# Statron_RP2040.net
KiCad netlist of a schematic drawn in Altium Designer
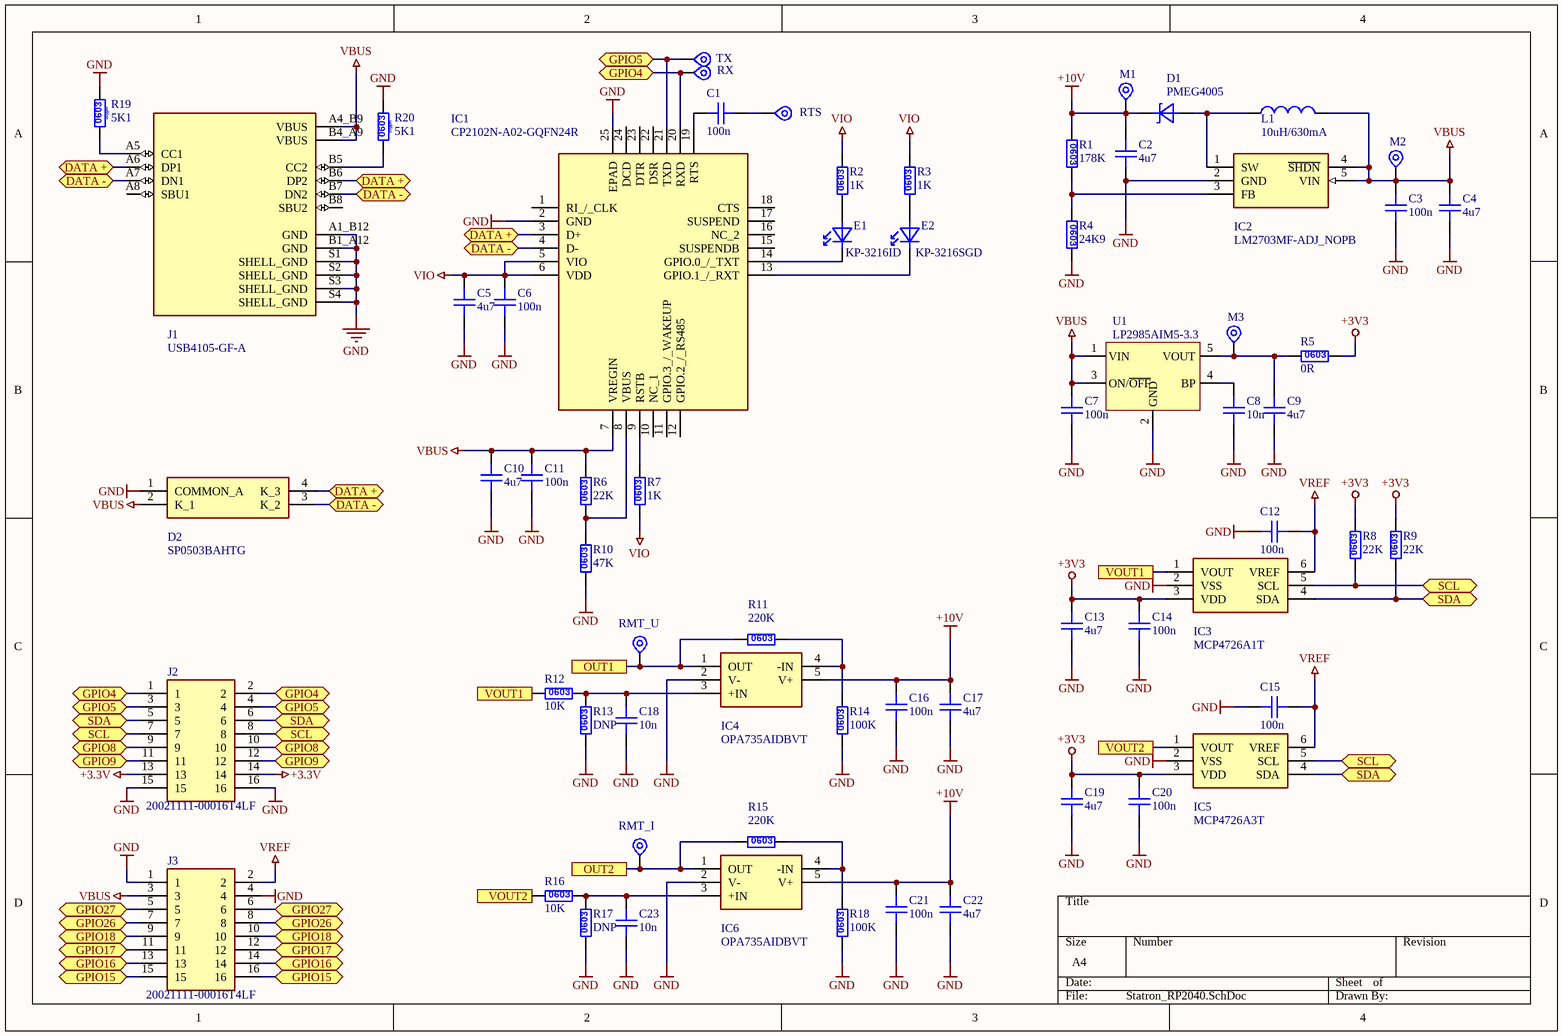
[diagram p0: Statron_RP2040.SchDoc]

(export (version "E")
  (design (tool "Eeschema 10.0.6"))
  (components
    (comp (ref "C1")
      (value "100n")
      (footprint "RP2040:C0603M")
      (description "Ceramic Capacitor X7R")
      (fields (field (name "MANUFACTURER") "VISHAY") (field (name "PART NUMBER") "100n/16V X7R C0603"))
      (libsource (lib "PCB_RP2040") (part "CMP-UN-000268-1"))
    )
    (comp (ref "C2")
      (value "4u7")
      (footprint "RP2040:C0603")
      (description "Ceramic Capacitor X5R")
      (fields (field (name "PART NUMBER") "GRM188R60J475KE19J") (field (name "MANUFACTURER") "Murata"))
      (libsource (lib "PCB_RP2040") (part "CMP-UN-000401-1"))
    )
    (comp (ref "C3")
      (value "100n")
      (footprint "RP2040:C0603M")
      (description "Ceramic Capacitor X7R")
      (fields (field (name "MANUFACTURER") "VISHAY") (field (name "PART NUMBER") "100n/16V X7R C0603"))
      (libsource (lib "PCB_RP2040") (part "CMP-UN-000268-1"))
    )
    (comp (ref "C4")
      (value "4u7")
      (footprint "RP2040:C0603")
      (description "Ceramic Capacitor X5R")
      (fields (field (name "PART NUMBER") "GRM188R60J475KE19J") (field (name "MANUFACTURER") "Murata"))
      (libsource (lib "PCB_RP2040") (part "CMP-UN-000401-1"))
    )
    (comp (ref "C5")
      (value "4u7")
      (footprint "RP2040:C0603")
      (description "Ceramic Capacitor X5R")
      (fields (field (name "PART NUMBER") "GRM188R60J475KE19J") (field (name "MANUFACTURER") "Murata"))
      (libsource (lib "PCB_RP2040") (part "CMP-UN-000401-1"))
    )
    (comp (ref "C6")
      (value "100n")
      (footprint "RP2040:C0603M")
      (description "Ceramic Capacitor X7R")
      (fields (field (name "MANUFACTURER") "VISHAY") (field (name "PART NUMBER") "100n/16V X7R C0603"))
      (libsource (lib "PCB_RP2040") (part "CMP-UN-000268-1"))
    )
    (comp (ref "C7")
      (value "100n")
      (footprint "RP2040:C0603M")
      (description "Ceramic Capacitor X7R")
      (fields (field (name "MANUFACTURER") "VISHAY") (field (name "PART NUMBER") "100n/16V X7R C0603"))
      (libsource (lib "PCB_RP2040") (part "UniversalCapacitor"))
    )
    (comp (ref "C8")
      (value "10n")
      (footprint "RP2040:C0603M")
      (description "Ceramic Capacitor X7R")
      (fields (field (name "MANUFACTURER") "VISHAY") (field (name "PART NUMBER") "10n/50V X7R C0603"))
      (libsource (lib "PCB_RP2040") (part "UniversalCapacitor"))
    )
    (comp (ref "C9")
      (value "4u7")
      (footprint "RP2040:C0603")
      (description "Ceramic Capacitor X5R")
      (fields (field (name "PART NUMBER") "GRM188R60J475KE19J") (field (name "MANUFACTURER") "Murata"))
      (libsource (lib "PCB_RP2040") (part "CMP-UN-000401-1"))
    )
    (comp (ref "C10")
      (value "4u7")
      (footprint "RP2040:C0603")
      (description "Ceramic Capacitor X5R")
      (fields (field (name "PART NUMBER") "GRM188R60J475KE19J") (field (name "MANUFACTURER") "Murata"))
      (libsource (lib "PCB_RP2040") (part "CMP-UN-000401-1"))
    )
    (comp (ref "C11")
      (value "100n")
      (footprint "RP2040:C0603M")
      (description "Ceramic Capacitor X7R")
      (fields (field (name "MANUFACTURER") "VISHAY") (field (name "PART NUMBER") "100n/16V X7R C0603"))
      (libsource (lib "PCB_RP2040") (part "CMP-UN-000268-1"))
    )
    (comp (ref "C12")
      (value "100n")
      (footprint "RP2040:C0603M")
      (description "Ceramic Capacitor X7R")
      (fields (field (name "MANUFACTURER") "VISHAY") (field (name "PART NUMBER") "100n/16V X7R C0603"))
      (libsource (lib "PCB_RP2040") (part "CMP-UN-000268-1"))
    )
    (comp (ref "C13")
      (value "4u7")
      (footprint "RP2040:C0603")
      (description "Ceramic Capacitor X5R")
      (fields (field (name "PART NUMBER") "GRM188R60J475KE19J") (field (name "MANUFACTURER") "Murata"))
      (libsource (lib "PCB_RP2040") (part "CMP-UN-000401-1"))
    )
    (comp (ref "C14")
      (value "100n")
      (footprint "RP2040:C0603M")
      (description "Ceramic Capacitor X7R")
      (fields (field (name "MANUFACTURER") "VISHAY") (field (name "PART NUMBER") "100n/16V X7R C0603"))
      (libsource (lib "PCB_RP2040") (part "CMP-UN-000268-1"))
    )
    (comp (ref "C15")
      (value "100n")
      (footprint "RP2040:C0603M")
      (description "Ceramic Capacitor X7R")
      (fields (field (name "MANUFACTURER") "VISHAY") (field (name "PART NUMBER") "100n/16V X7R C0603"))
      (libsource (lib "PCB_RP2040") (part "CMP-UN-000268-1"))
    )
    (comp (ref "C16")
      (value "100n")
      (footprint "RP2040:C0603M")
      (description "Ceramic Capacitor X7R")
      (fields (field (name "MANUFACTURER") "VISHAY") (field (name "PART NUMBER") "100n/16V X7R C0603"))
      (libsource (lib "PCB_RP2040") (part "CMP-UN-000268-1"))
    )
    (comp (ref "C17")
      (value "4u7")
      (footprint "RP2040:C0603")
      (description "Ceramic Capacitor X5R")
      (fields (field (name "PART NUMBER") "GRM188R60J475KE19J") (field (name "MANUFACTURER") "Murata"))
      (libsource (lib "PCB_RP2040") (part "CMP-UN-000401-1"))
    )
    (comp (ref "C18")
      (value "10n")
      (footprint "RP2040:C0603M")
      (description "Ceramic Capacitor X7R")
      (fields (field (name "MANUFACTURER") "VISHAY") (field (name "PART NUMBER") "10n/50V X7R C0603"))
      (libsource (lib "PCB_RP2040") (part "UniversalCapacitor"))
    )
    (comp (ref "C19")
      (value "4u7")
      (footprint "RP2040:C0603")
      (description "Ceramic Capacitor X5R")
      (fields (field (name "PART NUMBER") "GRM188R60J475KE19J") (field (name "MANUFACTURER") "Murata"))
      (libsource (lib "PCB_RP2040") (part "CMP-UN-000401-1"))
    )
    (comp (ref "C20")
      (value "100n")
      (footprint "RP2040:C0603M")
      (description "Ceramic Capacitor X7R")
      (fields (field (name "MANUFACTURER") "VISHAY") (field (name "PART NUMBER") "100n/16V X7R C0603"))
      (libsource (lib "PCB_RP2040") (part "CMP-UN-000268-1"))
    )
    (comp (ref "C21")
      (value "100n")
      (footprint "RP2040:C0603M")
      (description "Ceramic Capacitor X7R")
      (fields (field (name "MANUFACTURER") "VISHAY") (field (name "PART NUMBER") "100n/16V X7R C0603"))
      (libsource (lib "PCB_RP2040") (part "CMP-UN-000268-1"))
    )
    (comp (ref "C22")
      (value "4u7")
      (footprint "RP2040:C0603")
      (description "Ceramic Capacitor X5R")
      (fields (field (name "PART NUMBER") "GRM188R60J475KE19J") (field (name "MANUFACTURER") "Murata"))
      (libsource (lib "PCB_RP2040") (part "CMP-UN-000401-1"))
    )
    (comp (ref "C23")
      (value "10n")
      (footprint "RP2040:C0603M")
      (description "Ceramic Capacitor X7R")
      (fields (field (name "MANUFACTURER") "VISHAY") (field (name "PART NUMBER") "10n/50V X7R C0603"))
      (libsource (lib "PCB_RP2040") (part "UniversalCapacitor"))
    )
    (comp (ref "D1")
      (value "PMEG4005")
      (footprint "SOD323")
      (description "Schottky Diode 40V, 500mA")
      (fields (field (name "PART NUMBER") "PMEG4005AEA") (field (name "MANUFACTURER") "NXP"))
      (libsource (lib "UNIS") (part "ShotkyDiode"))
    )
    (comp (ref "D2")
      (value "SP0503BAHTG")
      (footprint "SamacSys:SP0503BAHTG")
      (description "TVS Diode (Uni-directional)")
      (libsource (lib "*") (part "SP0503BAHTG"))
    )
    (comp (ref "E1")
      (value "KP-3216ID")
      (footprint "LED1206 R")
      (description "SMD LED Red")
      (fields (field (name "MANUFACTURER") "KINGBRIGHT"))
      (libsource (lib "UNIS") (part "LED"))
    )
    (comp (ref "E2")
      (value "KP-3216SGD")
      (footprint "LED1206 G")
      (description "SMD LED Green")
      (fields (field (name "MANUFACTURER") "KINGBRIGHT"))
      (libsource (lib "UNIS") (part "LED"))
    )
    (comp (ref "IC1")
      (value "CP2102N-A02-GQFN24R")
      (footprint "SamacSys:QFN50P400X400X80-25N-D")
      (description "Integrated Circuit")
      (fields (field (name "MOUSER2 PART NUMBER") "634-CP2102NA02QFN24R"))
      (libsource (lib "*") (part "CP2102N-A02-GQFN24R"))
    )
    (comp (ref "IC2")
      (value "LM2703MF-ADJ_NOPB")
      (footprint "SamacSys:SOT95P280X145-5N")
      (description "Integrated Circuit")
      (fields (field (name "MANUFACTURER_PART_NUMBER") "LM2703MF-ADJ/NOPB"))
      (libsource (lib "*") (part "LM2703MF-ADJ_NOPB"))
    )
    (comp (ref "IC3")
      (value "MCP4726A1T")
      (footprint "SamacSys:SOT95P270X145-6N")
      (description "Integrated Circuit")
      (fields
        (field (name "MOUSER2 PART NUMBER") "579-MCP4726A3TECH")
        (field (name "MANUFACTURER_PART_NUMBER") "MCP4726A3T-E/CH")
      )
      (libsource (lib "*") (part "MCP4726A3T-E_CH"))
    )
    (comp (ref "IC4")
      (value "OPA735AIDBVT")
      (footprint "SamacSys:SOT95P280X145-5N")
      (description "Integrated Circuit")
      (fields (field (name "MOUSER2 PART NUMBER") "595-OPA735AIDBVT"))
      (libsource (lib "*") (part "OPA735AIDBVT"))
    )
    (comp (ref "IC5")
      (value "MCP4726A3T")
      (footprint "SamacSys:SOT95P270X145-6N")
      (description "Integrated Circuit")
      (fields
        (field (name "MOUSER2 PART NUMBER") "579-MCP4726A3TECH")
        (field (name "MANUFACTURER_PART_NUMBER") "MCP4726A3T-E/CH")
      )
      (libsource (lib "*") (part "MCP4726A3T-E_CH"))
    )
    (comp (ref "IC6")
      (value "OPA735AIDBVT")
      (footprint "SamacSys:SOT95P280X145-5N")
      (description "Integrated Circuit")
      (fields (field (name "MOUSER2 PART NUMBER") "595-OPA735AIDBVT"))
      (libsource (lib "*") (part "OPA735AIDBVT"))
    )
    (comp (ref "J1")
      (value "USB4105-GF-A")
      (footprint "GCT_USB4105-GF-A")
      (fields (field (name "MF") "GCT"))
      (libsource (lib "USB4105-GF-A") (part "USB4105-GF-A"))
    )
    (comp (ref "J2")
      (value "20021111-00016T4LF")
      (footprint "SamacSys:2002111100016T4LF")
      (description "Connector")
      (libsource (lib "*") (part "20021111-00016T4LF"))
    )
    (comp (ref "J3")
      (value "20021111-00016T4LF")
      (footprint "SamacSys:2002111100016T4LF")
      (description "Connector")
      (libsource (lib "*") (part "20021111-00016T4LF"))
    )
    (comp (ref "L1")
      (value "10uH/630mA")
      (footprint "L_HEXAGON_2.8x2.8_H1.3_SMD_WE-TPC_2813")
      (description "SMT power inductor WE-TPC_2813")
      (fields (field (name "MANUFACTURER") "Würt Elektronik") (field (name "PART NUMBER") "744029100"))
      (libsource (lib "UNIS") (part "UniversalInductor"))
    )
    (comp (ref "M1")
      (value "TP")
      (footprint "RP2040:Pad 1mm SMD")
      (description "Test Point")
      (libsource (lib "PCB_RP2040") (part "M Point"))
    )
    (comp (ref "M2")
      (value "TP")
      (footprint "RP2040:Pad 1mm SMD")
      (description "Test Point")
      (libsource (lib "PCB_RP2040") (part "M Point"))
    )
    (comp (ref "M3")
      (value "TP")
      (footprint "RP2040:Pad 1mm SMD")
      (description "Test Point")
      (libsource (lib "PCB_RP2040") (part "M Point"))
    )
    (comp (ref "R1")
      (value "178K")
      (footprint "R0603")
      (description "Resistor 1%, 0.1W, 75V")
      (fields (field (name "PART NUMBER") "180K R0603") (field (name "MANUFACTURER") "VISHAY"))
      (libsource (lib "UNIS") (part "UniversalResistor"))
    )
    (comp (ref "R2")
      (value "1K")
      (footprint "RP2040:R0603")
      (description "Resistor 1%, 0.1W, 75V")
      (fields (field (name "MANUFACTURER") "Vishay Dale") (field (name "PART NUMBER") "1K R0603"))
      (libsource (lib "PCB_RP2040") (part "CMP-UN-001963-2"))
    )
    (comp (ref "R3")
      (value "1K")
      (footprint "RP2040:R0603")
      (description "Resistor 1%, 0.1W, 75V")
      (fields (field (name "MANUFACTURER") "Vishay Dale") (field (name "PART NUMBER") "1K R0603"))
      (libsource (lib "PCB_RP2040") (part "CMP-UN-001963-2"))
    )
    (comp (ref "R4")
      (value "24K9")
      (footprint "R0603")
      (description "Resistor 1%, 0.1W, 75V")
      (fields (field (name "PART NUMBER") "27K R0603") (field (name "MANUFACTURER") "VISHAY"))
      (libsource (lib "UNIS") (part "UniversalResistor"))
    )
    (comp (ref "R5")
      (value "0R")
      (footprint "R0603")
      (description "Resistor 1%, 0.1W, 75V")
      (fields (field (name "PART NUMBER") "0R R0603") (field (name "MANUFACTURER") "VISHAY"))
      (libsource (lib "UNIS") (part "UniversalResistor"))
    )
    (comp (ref "R6")
      (value "22K")
      (footprint "R0603")
      (description "Resistor 1%, 0.1W, 75V")
      (fields (field (name "PART NUMBER") "22K R0603") (field (name "MANUFACTURER") "VISHAY"))
      (libsource (lib "UNIS") (part "UniversalResistor"))
    )
    (comp (ref "R7")
      (value "1K")
      (footprint "RP2040:R0603")
      (description "Resistor 1%, 0.1W, 75V")
      (fields (field (name "MANUFACTURER") "Vishay Dale") (field (name "PART NUMBER") "1K R0603"))
      (libsource (lib "PCB_RP2040") (part "CMP-UN-001963-2"))
    )
    (comp (ref "R8")
      (value "22K")
      (footprint "R0603")
      (description "Resistor 1%, 0.1W, 75V")
      (fields (field (name "PART NUMBER") "22K R0603") (field (name "MANUFACTURER") "VISHAY"))
      (libsource (lib "UNIS") (part "UniversalResistor"))
    )
    (comp (ref "R9")
      (value "22K")
      (footprint "R0603")
      (description "Resistor 1%, 0.1W, 75V")
      (fields (field (name "PART NUMBER") "22K R0603") (field (name "MANUFACTURER") "VISHAY"))
      (libsource (lib "UNIS") (part "UniversalResistor"))
    )
    (comp (ref "R10")
      (value "47K")
      (footprint "R0603")
      (description "Resistor 1%, 0.1W, 75V")
      (fields (field (name "MANUFACTURER") "VISHAY") (field (name "PART NUMBER") "47K R0603"))
      (libsource (lib "UNIS") (part "UniversalResistor"))
    )
    (comp (ref "R11")
      (value "220K")
      (footprint "R0603")
      (description "Resistor 1%, 0.1W, 75V")
      (fields (field (name "PART NUMBER") "22K R0603") (field (name "MANUFACTURER") "VISHAY"))
      (libsource (lib "UNIS") (part "UniversalResistor"))
    )
    (comp (ref "R12")
      (value "10K")
      (footprint "RP2040:R0603")
      (description "Resistor 1%, 0.1W, 75V")
      (fields (field (name "PART NUMBER") "10K R0603") (field (name "MANUFACTURER") "Vishay Semiconductors"))
      (libsource (lib "PCB_RP2040") (part "CMP-UN-001953-2"))
    )
    (comp (ref "R13")
      (value "DNP")
      (footprint "RP2040:R0603")
      (description "Resistor 1%, 0.1W, 75V")
      (fields (field (name "PART NUMBER") "10K R0603") (field (name "MANUFACTURER") "Vishay Semiconductors"))
      (libsource (lib "PCB_RP2040") (part "CMP-UN-001953-2"))
    )
    (comp (ref "R14")
      (value "100K")
      (footprint "RP2040:R0603")
      (description "Resistor 1%, 0.1W, 75V")
      (fields (field (name "PART NUMBER") "10K R0603") (field (name "MANUFACTURER") "Vishay Semiconductors"))
      (libsource (lib "PCB_RP2040") (part "CMP-UN-001953-2"))
    )
    (comp (ref "R15")
      (value "220K")
      (footprint "R0603")
      (description "Resistor 1%, 0.1W, 75V")
      (fields (field (name "PART NUMBER") "22K R0603") (field (name "MANUFACTURER") "VISHAY"))
      (libsource (lib "UNIS") (part "UniversalResistor"))
    )
    (comp (ref "R16")
      (value "10K")
      (footprint "RP2040:R0603")
      (description "Resistor 1%, 0.1W, 75V")
      (fields (field (name "PART NUMBER") "10K R0603") (field (name "MANUFACTURER") "Vishay Semiconductors"))
      (libsource (lib "PCB_RP2040") (part "CMP-UN-001953-2"))
    )
    (comp (ref "R17")
      (value "DNP")
      (footprint "RP2040:R0603")
      (description "Resistor 1%, 0.1W, 75V")
      (fields (field (name "PART NUMBER") "10K R0603") (field (name "MANUFACTURER") "Vishay Semiconductors"))
      (libsource (lib "PCB_RP2040") (part "CMP-UN-001953-2"))
    )
    (comp (ref "R18")
      (value "100K")
      (footprint "RP2040:R0603")
      (description "Resistor 1%, 0.1W, 75V")
      (fields (field (name "PART NUMBER") "10K R0603") (field (name "MANUFACTURER") "Vishay Semiconductors"))
      (libsource (lib "PCB_RP2040") (part "CMP-UN-001953-2"))
    )
    (comp (ref "R19")
      (value "5K1")
      (footprint "R0603")
      (description "Resistor 1%, 0.1W, 75V, 50ppm")
      (fields (field (name "MANUFACTURER") "Vishay") (field (name "PART NUMBER") "CRCW060356K0FHEAP"))
      (libsource (lib "UNIS") (part "UniversalResistor-50ppm"))
    )
    (comp (ref "R20")
      (value "5K1")
      (footprint "R0603")
      (description "Resistor 1%, 0.1W, 75V, 50ppm")
      (fields (field (name "MANUFACTURER") "Vishay") (field (name "PART NUMBER") "CRCW060356K0FHEAP"))
      (libsource (lib "UNIS") (part "UniversalResistor-50ppm"))
    )
    (comp (ref "RMT_I")
      (value "TP")
      (footprint "RP2040:Pad0.6mm")
      (description "Test Point")
      (libsource (lib "PCB_RP2040") (part "CMP-UN-002500-5"))
    )
    (comp (ref "RMT_U")
      (value "TP")
      (footprint "RP2040:Pad0.6mm")
      (description "Test Point")
      (libsource (lib "PCB_RP2040") (part "CMP-UN-002500-5"))
    )
    (comp (ref "RTS")
      (value "TP")
      (footprint "RP2040:Pad0.6mm")
      (description "Test Point")
      (libsource (lib "PCB_RP2040") (part "CMP-UN-002500-5"))
    )
    (comp (ref "RX")
      (value "TP")
      (footprint "RP2040:Pad0.6mm")
      (description "Test Point")
      (libsource (lib "PCB_RP2040") (part "CMP-UN-002500-5"))
    )
    (comp (ref "TX")
      (value "TP")
      (footprint "RP2040:Pad0.6mm")
      (description "Test Point")
      (libsource (lib "PCB_RP2040") (part "CMP-UN-002500-5"))
    )
    (comp (ref "U1")
      (value "LP2985AIM5-3.3")
      (footprint "RP2040:SOT23-5")
      (description "150-mA , Low-Dropout Regulator")
      (fields
        (field (name "MANUFACTURER") "Texas Instruments")
        (field (name "PART NUMBER") "LP2985AIM5-3.3/NOPB")
      )
      (libsource (lib "PCB_RP2040") (part "LP2985_SOT25"))
    )
  )
  (nets
    (net (code "1") (name "+3.3V") (class "Default")
      (node (ref "J2") (pin "13") (pinfunction "13_13") (pintype "passive"))
      (node (ref "J2") (pin "14") (pinfunction "14_14") (pintype "passive"))
    )
    (net (code "2") (name "+3V3") (class "Default")
      (node (ref "C13") (pin "2") (pinfunction "2_2") (pintype "passive"))
      (node (ref "C14") (pin "2") (pinfunction "2_2") (pintype "passive"))
      (node (ref "C19") (pin "2") (pinfunction "2_2") (pintype "passive"))
      (node (ref "C20") (pin "2") (pinfunction "2_2") (pintype "passive"))
      (node (ref "IC3") (pin "3") (pinfunction "VDD_3") (pintype "passive"))
      (node (ref "IC5") (pin "3") (pinfunction "VDD_3") (pintype "passive"))
      (node (ref "R5") (pin "1") (pinfunction "1_1") (pintype "passive"))
      (node (ref "R8") (pin "1") (pinfunction "1_1") (pintype "passive"))
      (node (ref "R9") (pin "1") (pinfunction "1_1") (pintype "passive"))
    )
    (net (code "3") (name "+10V") (class "Default")
      (node (ref "C16") (pin "1") (pinfunction "1_1") (pintype "passive"))
      (node (ref "C17") (pin "2") (pinfunction "2_2") (pintype "passive"))
      (node (ref "C2") (pin "2") (pinfunction "2_2") (pintype "passive"))
      (node (ref "C21") (pin "1") (pinfunction "1_1") (pintype "passive"))
      (node (ref "C22") (pin "2") (pinfunction "2_2") (pintype "passive"))
      (node (ref "D1") (pin "2") (pinfunction "C_2") (pintype "passive"))
      (node (ref "IC4") (pin "5") (pinfunction "V+_5") (pintype "passive"))
      (node (ref "IC6") (pin "5") (pinfunction "V+_5") (pintype "passive"))
      (node (ref "M1") (pin "1") (pinfunction "1_1") (pintype "passive"))
      (node (ref "R1") (pin "2") (pinfunction "2_2") (pintype "passive"))
    )
    (net (code "4") (name "/DATA +") (class "Default")
      (node (ref "D2") (pin "4") (pinfunction "K_3_4") (pintype "passive"))
      (node (ref "IC1") (pin "3") (pinfunction "D+_3") (pintype "passive"))
      (node (ref "J1") (pin "A6") (pinfunction "DP1_A6") (pintype "bidirectional"))
      (node (ref "J1") (pin "B6") (pinfunction "DP2_B6") (pintype "bidirectional"))
    )
    (net (code "5") (name "/DATA -") (class "Default")
      (node (ref "D2") (pin "3") (pinfunction "K_2_3") (pintype "passive"))
      (node (ref "IC1") (pin "4") (pinfunction "D-_4") (pintype "passive"))
      (node (ref "J1") (pin "A7") (pinfunction "DN1_A7") (pintype "bidirectional"))
      (node (ref "J1") (pin "B7") (pinfunction "DN2_B7") (pintype "bidirectional"))
    )
    (net (code "6") (name "/GPIO4") (class "Default")
      (node (ref "IC1") (pin "20") (pinfunction "RXD_20") (pintype "passive"))
      (node (ref "J2") (pin "1") (pinfunction "1_1") (pintype "passive"))
      (node (ref "J2") (pin "2") (pinfunction "2_2") (pintype "passive"))
      (node (ref "RX") (pin "1") (pinfunction "1_1") (pintype "passive"))
    )
    (net (code "7") (name "/GPIO5") (class "Default")
      (node (ref "IC1") (pin "21") (pinfunction "TXD_21") (pintype "passive"))
      (node (ref "J2") (pin "3") (pinfunction "3_3") (pintype "passive"))
      (node (ref "J2") (pin "4") (pinfunction "4_4") (pintype "passive"))
      (node (ref "TX") (pin "1") (pinfunction "1_1") (pintype "passive"))
    )
    (net (code "8") (name "/GPIO8") (class "Default")
      (node (ref "J2") (pin "10") (pinfunction "10_10") (pintype "passive"))
      (node (ref "J2") (pin "9") (pinfunction "9_9") (pintype "passive"))
    )
    (net (code "9") (name "/GPIO9") (class "Default")
      (node (ref "J2") (pin "11") (pinfunction "11_11") (pintype "passive"))
      (node (ref "J2") (pin "12") (pinfunction "12_12") (pintype "passive"))
    )
    (net (code "10") (name "/GPIO15") (class "Default")
      (node (ref "J3") (pin "15") (pinfunction "15_15") (pintype "passive"))
      (node (ref "J3") (pin "16") (pinfunction "16_16") (pintype "passive"))
    )
    (net (code "11") (name "/GPIO16") (class "Default")
      (node (ref "J3") (pin "13") (pinfunction "13_13") (pintype "passive"))
      (node (ref "J3") (pin "14") (pinfunction "14_14") (pintype "passive"))
    )
    (net (code "12") (name "/GPIO17") (class "Default")
      (node (ref "J3") (pin "11") (pinfunction "11_11") (pintype "passive"))
      (node (ref "J3") (pin "12") (pinfunction "12_12") (pintype "passive"))
    )
    (net (code "13") (name "/GPIO18") (class "Default")
      (node (ref "J3") (pin "10") (pinfunction "10_10") (pintype "passive"))
      (node (ref "J3") (pin "9") (pinfunction "9_9") (pintype "passive"))
    )
    (net (code "14") (name "/GPIO26") (class "Default")
      (node (ref "J3") (pin "7") (pinfunction "7_7") (pintype "passive"))
      (node (ref "J3") (pin "8") (pinfunction "8_8") (pintype "passive"))
    )
    (net (code "15") (name "/GPIO27") (class "Default")
      (node (ref "J3") (pin "5") (pinfunction "5_5") (pintype "passive"))
      (node (ref "J3") (pin "6") (pinfunction "6_6") (pintype "passive"))
    )
    (net (code "16") (name "/OUT1") (class "Default")
      (node (ref "IC4") (pin "1") (pinfunction "OUT_1") (pintype "passive"))
      (node (ref "R11") (pin "2") (pinfunction "2_2") (pintype "passive"))
      (node (ref "RMT_U") (pin "1") (pinfunction "1_1") (pintype "passive"))
    )
    (net (code "17") (name "/OUT2") (class "Default")
      (node (ref "IC6") (pin "1") (pinfunction "OUT_1") (pintype "passive"))
      (node (ref "R15") (pin "2") (pinfunction "2_2") (pintype "passive"))
      (node (ref "RMT_I") (pin "1") (pinfunction "1_1") (pintype "passive"))
    )
    (net (code "18") (name "/SCL") (class "Default")
      (node (ref "IC3") (pin "5") (pinfunction "SCL_5") (pintype "passive"))
      (node (ref "IC5") (pin "5") (pinfunction "SCL_5") (pintype "passive"))
      (node (ref "J2") (pin "7") (pinfunction "7_7") (pintype "passive"))
      (node (ref "J2") (pin "8") (pinfunction "8_8") (pintype "passive"))
      (node (ref "R8") (pin "2") (pinfunction "2_2") (pintype "passive"))
    )
    (net (code "19") (name "/SDA") (class "Default")
      (node (ref "IC3") (pin "4") (pinfunction "SDA_4") (pintype "passive"))
      (node (ref "IC5") (pin "4") (pinfunction "SDA_4") (pintype "passive"))
      (node (ref "J2") (pin "5") (pinfunction "5_5") (pintype "passive"))
      (node (ref "J2") (pin "6") (pinfunction "6_6") (pintype "passive"))
      (node (ref "R9") (pin "2") (pinfunction "2_2") (pintype "passive"))
    )
    (net (code "20") (name "/VOUT1") (class "Default")
      (node (ref "IC3") (pin "1") (pinfunction "VOUT_1") (pintype "passive"))
      (node (ref "R12") (pin "2") (pinfunction "2_2") (pintype "passive"))
    )
    (net (code "21") (name "/VOUT2") (class "Default")
      (node (ref "IC5") (pin "1") (pinfunction "VOUT_1") (pintype "passive"))
      (node (ref "R16") (pin "2") (pinfunction "2_2") (pintype "passive"))
    )
    (net (code "22") (name "GND") (class "Default")
      (node (ref "C10") (pin "2") (pinfunction "2_2") (pintype "passive"))
      (node (ref "C11") (pin "2") (pinfunction "2_2") (pintype "passive"))
      (node (ref "C12") (pin "2") (pinfunction "2_2") (pintype "passive"))
      (node (ref "C13") (pin "1") (pinfunction "1_1") (pintype "passive"))
      (node (ref "C14") (pin "1") (pinfunction "1_1") (pintype "passive"))
      (node (ref "C15") (pin "2") (pinfunction "2_2") (pintype "passive"))
      (node (ref "C16") (pin "2") (pinfunction "2_2") (pintype "passive"))
      (node (ref "C17") (pin "1") (pinfunction "1_1") (pintype "passive"))
      (node (ref "C18") (pin "2") (pinfunction "2_2") (pintype "passive"))
      (node (ref "C19") (pin "1") (pinfunction "1_1") (pintype "passive"))
      (node (ref "C2") (pin "1") (pinfunction "1_1") (pintype "passive"))
      (node (ref "C20") (pin "1") (pinfunction "1_1") (pintype "passive"))
      (node (ref "C21") (pin "2") (pinfunction "2_2") (pintype "passive"))
      (node (ref "C22") (pin "1") (pinfunction "1_1") (pintype "passive"))
      (node (ref "C23") (pin "2") (pinfunction "2_2") (pintype "passive"))
      (node (ref "C3") (pin "2") (pinfunction "2_2") (pintype "passive"))
      (node (ref "C4") (pin "2") (pinfunction "2_2") (pintype "passive"))
      (node (ref "C5") (pin "2") (pinfunction "2_2") (pintype "passive"))
      (node (ref "C6") (pin "2") (pinfunction "2_2") (pintype "passive"))
      (node (ref "C7") (pin "2") (pinfunction "2_2") (pintype "passive"))
      (node (ref "C8") (pin "2") (pinfunction "2_2") (pintype "passive"))
      (node (ref "C9") (pin "2") (pinfunction "2_2") (pintype "passive"))
      (node (ref "D2") (pin "1") (pinfunction "COMMON_A_1") (pintype "passive"))
      (node (ref "IC1") (pin "2") (pinfunction "GND_2") (pintype "passive"))
      (node (ref "IC1") (pin "25") (pinfunction "EPAD_25") (pintype "passive"))
      (node (ref "IC2") (pin "2") (pinfunction "GND_2") (pintype "power_in"))
      (node (ref "IC3") (pin "2") (pinfunction "VSS_2") (pintype "passive"))
      (node (ref "IC4") (pin "2") (pinfunction "V-_2") (pintype "passive"))
      (node (ref "IC5") (pin "2") (pinfunction "VSS_2") (pintype "passive"))
      (node (ref "IC6") (pin "2") (pinfunction "V-_2") (pintype "passive"))
      (node (ref "J1") (pin "A1_B12") (pinfunction "GND_A1_B12") (pintype "power_in"))
      (node (ref "J1") (pin "B1_A12") (pinfunction "GND_B1_A12") (pintype "power_in"))
      (node (ref "J1") (pin "S1") (pinfunction "SHELL_GND_S1") (pintype "power_in"))
      (node (ref "J1") (pin "S2") (pinfunction "SHELL_GND_S2") (pintype "power_in"))
      (node (ref "J1") (pin "S3") (pinfunction "SHELL_GND_S3") (pintype "power_in"))
      (node (ref "J1") (pin "S4") (pinfunction "SHELL_GND_S4") (pintype "power_in"))
      (node (ref "J2") (pin "15") (pinfunction "15_15") (pintype "passive"))
      (node (ref "J2") (pin "16") (pinfunction "16_16") (pintype "passive"))
      (node (ref "J3") (pin "1") (pinfunction "1_1") (pintype "passive"))
      (node (ref "J3") (pin "4") (pinfunction "4_4") (pintype "passive"))
      (node (ref "R10") (pin "2") (pinfunction "2_2") (pintype "passive"))
      (node (ref "R13") (pin "2") (pinfunction "2_2") (pintype "passive"))
      (node (ref "R14") (pin "2") (pinfunction "2_2") (pintype "passive"))
      (node (ref "R17") (pin "2") (pinfunction "2_2") (pintype "passive"))
      (node (ref "R18") (pin "2") (pinfunction "2_2") (pintype "passive"))
      (node (ref "R19") (pin "1") (pinfunction "1_1") (pintype "passive"))
      (node (ref "R20") (pin "1") (pinfunction "1_1") (pintype "passive"))
      (node (ref "R4") (pin "1") (pinfunction "1_1") (pintype "passive"))
      (node (ref "U1") (pin "2") (pinfunction "GND_2") (pintype "power_in"))
    )
    (net (code "23") (name "Net-(C1-Pad1)") (class "Default")
      (node (ref "C1") (pin "1") (pinfunction "1_1") (pintype "passive"))
      (node (ref "RTS") (pin "1") (pinfunction "1_1") (pintype "passive"))
    )
    (net (code "24") (name "Net-(D1-A)") (class "Default")
      (node (ref "D1") (pin "1") (pinfunction "A_1") (pintype "passive"))
      (node (ref "IC2") (pin "1") (pinfunction "SW_1") (pintype "passive"))
      (node (ref "L1") (pin "1") (pinfunction "1_1") (pintype "passive"))
    )
    (net (code "25") (name "Net-(E1-A)") (class "Default")
      (node (ref "E1") (pin "1") (pinfunction "A_1") (pintype "passive"))
      (node (ref "R2") (pin "2") (pinfunction "2_2") (pintype "passive"))
    )
    (net (code "26") (name "Net-(E1-C)") (class "Default")
      (node (ref "E1") (pin "2") (pinfunction "C_2") (pintype "passive"))
      (node (ref "IC1") (pin "14") (pinfunction "GPIO.0_/_TXT_14") (pintype "passive"))
    )
    (net (code "27") (name "Net-(E2-A)") (class "Default")
      (node (ref "E2") (pin "1") (pinfunction "A_1") (pintype "passive"))
      (node (ref "R3") (pin "2") (pinfunction "2_2") (pintype "passive"))
    )
    (net (code "28") (name "Net-(E2-C)") (class "Default")
      (node (ref "E2") (pin "2") (pinfunction "C_2") (pintype "passive"))
      (node (ref "IC1") (pin "13") (pinfunction "GPIO.1_/_RXT_13") (pintype "passive"))
    )
    (net (code "29") (name "Net-(IC1-RSTB)") (class "Default")
      (node (ref "IC1") (pin "9") (pinfunction "RSTB_9") (pintype "passive"))
      (node (ref "R7") (pin "1") (pinfunction "1_1") (pintype "passive"))
    )
    (net (code "30") (name "Net-(IC1-RTS)") (class "Default")
      (node (ref "C1") (pin "2") (pinfunction "2_2") (pintype "passive"))
      (node (ref "IC1") (pin "19") (pinfunction "RTS_19") (pintype "passive"))
    )
    (net (code "31") (name "Net-(IC1-VBUS)") (class "Default")
      (node (ref "IC1") (pin "8") (pinfunction "VBUS_8") (pintype "passive"))
      (node (ref "R10") (pin "1") (pinfunction "1_1") (pintype "passive"))
      (node (ref "R6") (pin "2") (pinfunction "2_2") (pintype "passive"))
    )
    (net (code "32") (name "Net-(IC2-FB)") (class "Default")
      (node (ref "IC2") (pin "3") (pinfunction "FB_3") (pintype "passive"))
      (node (ref "R1") (pin "1") (pinfunction "1_1") (pintype "passive"))
      (node (ref "R4") (pin "2") (pinfunction "2_2") (pintype "passive"))
    )
    (net (code "33") (name "Net-(IC4-+IN)") (class "Default")
      (node (ref "C18") (pin "1") (pinfunction "1_1") (pintype "passive"))
      (node (ref "IC4") (pin "3") (pinfunction "+IN_3") (pintype "passive"))
      (node (ref "R12") (pin "1") (pinfunction "1_1") (pintype "passive"))
      (node (ref "R13") (pin "1") (pinfunction "1_1") (pintype "passive"))
    )
    (net (code "34") (name "Net-(IC4--IN)") (class "Default")
      (node (ref "IC4") (pin "4") (pinfunction "-IN_4") (pintype "passive"))
      (node (ref "R11") (pin "1") (pinfunction "1_1") (pintype "passive"))
      (node (ref "R14") (pin "1") (pinfunction "1_1") (pintype "passive"))
    )
    (net (code "35") (name "Net-(IC6-+IN)") (class "Default")
      (node (ref "C23") (pin "1") (pinfunction "1_1") (pintype "passive"))
      (node (ref "IC6") (pin "3") (pinfunction "+IN_3") (pintype "passive"))
      (node (ref "R16") (pin "1") (pinfunction "1_1") (pintype "passive"))
      (node (ref "R17") (pin "1") (pinfunction "1_1") (pintype "passive"))
    )
    (net (code "36") (name "Net-(IC6--IN)") (class "Default")
      (node (ref "IC6") (pin "4") (pinfunction "-IN_4") (pintype "passive"))
      (node (ref "R15") (pin "1") (pinfunction "1_1") (pintype "passive"))
      (node (ref "R18") (pin "1") (pinfunction "1_1") (pintype "passive"))
    )
    (net (code "37") (name "Net-(J1-CC1)") (class "Default")
      (node (ref "J1") (pin "A5") (pinfunction "CC1_A5") (pintype "bidirectional"))
      (node (ref "R19") (pin "2") (pinfunction "2_2") (pintype "passive"))
    )
    (net (code "38") (name "Net-(J1-CC2)") (class "Default")
      (node (ref "J1") (pin "B5") (pinfunction "CC2_B5") (pintype "bidirectional"))
      (node (ref "R20") (pin "2") (pinfunction "2_2") (pintype "passive"))
    )
    (net (code "39") (name "Net-(U1-BP)") (class "Default")
      (node (ref "C8") (pin "1") (pinfunction "1_1") (pintype "passive"))
      (node (ref "U1") (pin "4") (pinfunction "BP_4") (pintype "passive"))
    )
    (net (code "40") (name "Net-(U1-VOUT)") (class "Default")
      (node (ref "C9") (pin "1") (pinfunction "1_1") (pintype "passive"))
      (node (ref "M3") (pin "1") (pinfunction "1_1") (pintype "passive"))
      (node (ref "R5") (pin "2") (pinfunction "2_2") (pintype "passive"))
      (node (ref "U1") (pin "5") (pinfunction "VOUT_5") (pintype "power_in"))
    )
    (net (code "41") (name "VBUS") (class "Default")
      (node (ref "C10") (pin "1") (pinfunction "1_1") (pintype "passive"))
      (node (ref "C11") (pin "1") (pinfunction "1_1") (pintype "passive"))
      (node (ref "C3") (pin "1") (pinfunction "1_1") (pintype "passive"))
      (node (ref "C4") (pin "1") (pinfunction "1_1") (pintype "passive"))
      (node (ref "C7") (pin "1") (pinfunction "1_1") (pintype "passive"))
      (node (ref "D2") (pin "2") (pinfunction "K_1_2") (pintype "passive"))
      (node (ref "IC1") (pin "7") (pinfunction "VREGIN_7") (pintype "passive"))
      (node (ref "IC2") (pin "4") (pinfunction "~{SHDN}_4") (pintype "passive"))
      (node (ref "IC2") (pin "5") (pinfunction "VIN_5") (pintype "input"))
      (node (ref "J1") (pin "A4_B9") (pinfunction "VBUS_A4_B9") (pintype "power_in"))
      (node (ref "J1") (pin "B4_A9") (pinfunction "VBUS_B4_A9") (pintype "power_in"))
      (node (ref "J3") (pin "3") (pinfunction "3_3") (pintype "passive"))
      (node (ref "L1") (pin "2") (pinfunction "2_2") (pintype "passive"))
      (node (ref "M2") (pin "1") (pinfunction "1_1") (pintype "passive"))
      (node (ref "R6") (pin "1") (pinfunction "1_1") (pintype "passive"))
      (node (ref "U1") (pin "1") (pinfunction "VIN_1") (pintype "power_in"))
      (node (ref "U1") (pin "3") (pinfunction "ON/~{OFF}_3") (pintype "passive"))
    )
    (net (code "42") (name "VIO") (class "Default")
      (node (ref "C5") (pin "1") (pinfunction "1_1") (pintype "passive"))
      (node (ref "C6") (pin "1") (pinfunction "1_1") (pintype "passive"))
      (node (ref "IC1") (pin "5") (pinfunction "VIO_5") (pintype "passive"))
      (node (ref "IC1") (pin "6") (pinfunction "VDD_6") (pintype "passive"))
      (node (ref "R2") (pin "1") (pinfunction "1_1") (pintype "passive"))
      (node (ref "R3") (pin "1") (pinfunction "1_1") (pintype "passive"))
      (node (ref "R7") (pin "2") (pinfunction "2_2") (pintype "passive"))
    )
    (net (code "43") (name "VREF") (class "Default")
      (node (ref "C12") (pin "1") (pinfunction "1_1") (pintype "passive"))
      (node (ref "C15") (pin "1") (pinfunction "1_1") (pintype "passive"))
      (node (ref "IC3") (pin "6") (pinfunction "VREF_6") (pintype "passive"))
      (node (ref "IC5") (pin "6") (pinfunction "VREF_6") (pintype "passive"))
      (node (ref "J3") (pin "2") (pinfunction "2_2") (pintype "passive"))
    )
    (net (code "44") (name "unconnected-(IC1-CTS-Pad18)") (class "Default")
      (node (ref "IC1") (pin "18") (pinfunction "CTS_18") (pintype "passive"))
    )
    (net (code "45") (name "unconnected-(IC1-DCD-Pad24)") (class "Default")
      (node (ref "IC1") (pin "24") (pinfunction "DCD_24") (pintype "passive"))
    )
    (net (code "46") (name "unconnected-(IC1-DSR-Pad22)") (class "Default")
      (node (ref "IC1") (pin "22") (pinfunction "DSR_22") (pintype "passive"))
    )
    (net (code "47") (name "unconnected-(IC1-DTR-Pad23)") (class "Default")
      (node (ref "IC1") (pin "23") (pinfunction "DTR_23") (pintype "passive"))
    )
    (net (code "48") (name "unconnected-(IC1-GPIO.2_{slash}_RS485-Pad12)") (class "Default")
      (node (ref "IC1") (pin "12") (pinfunction "GPIO.2_/_RS485_12") (pintype "passive"))
    )
    (net (code "49") (name "unconnected-(IC1-GPIO.3_{slash}_WAKEUP-Pad11)") (class "Default")
      (node (ref "IC1") (pin "11") (pinfunction "GPIO.3_/_WAKEUP_11") (pintype "passive"))
    )
    (net (code "50") (name "unconnected-(IC1-NC_1-Pad10)") (class "Default")
      (node (ref "IC1") (pin "10") (pinfunction "NC_1_10") (pintype "passive"))
    )
    (net (code "51") (name "unconnected-(IC1-NC_2-Pad16)") (class "Default")
      (node (ref "IC1") (pin "16") (pinfunction "NC_2_16") (pintype "passive"))
    )
    (net (code "52") (name "unconnected-(IC1-RI_{slash}_CLK-Pad1)") (class "Default")
      (node (ref "IC1") (pin "1") (pinfunction "RI_/_CLK_1") (pintype "passive"))
    )
    (net (code "53") (name "unconnected-(IC1-SUSPEND-Pad17)") (class "Default")
      (node (ref "IC1") (pin "17") (pinfunction "SUSPEND_17") (pintype "passive"))
    )
    (net (code "54") (name "unconnected-(IC1-SUSPENDB-Pad15)") (class "Default")
      (node (ref "IC1") (pin "15") (pinfunction "SUSPENDB_15") (pintype "passive"))
    )
    (net (code "55") (name "unconnected-(J1-SBU1-PadA8)") (class "Default")
      (node (ref "J1") (pin "A8") (pinfunction "SBU1_A8") (pintype "bidirectional"))
    )
    (net (code "56") (name "unconnected-(J1-SBU2-PadB8)") (class "Default")
      (node (ref "J1") (pin "B8") (pinfunction "SBU2_B8") (pintype "bidirectional"))
    )
  )
)
